# SoC_Control.net
KiCad netlist of a schematic drawn in Altium Designer
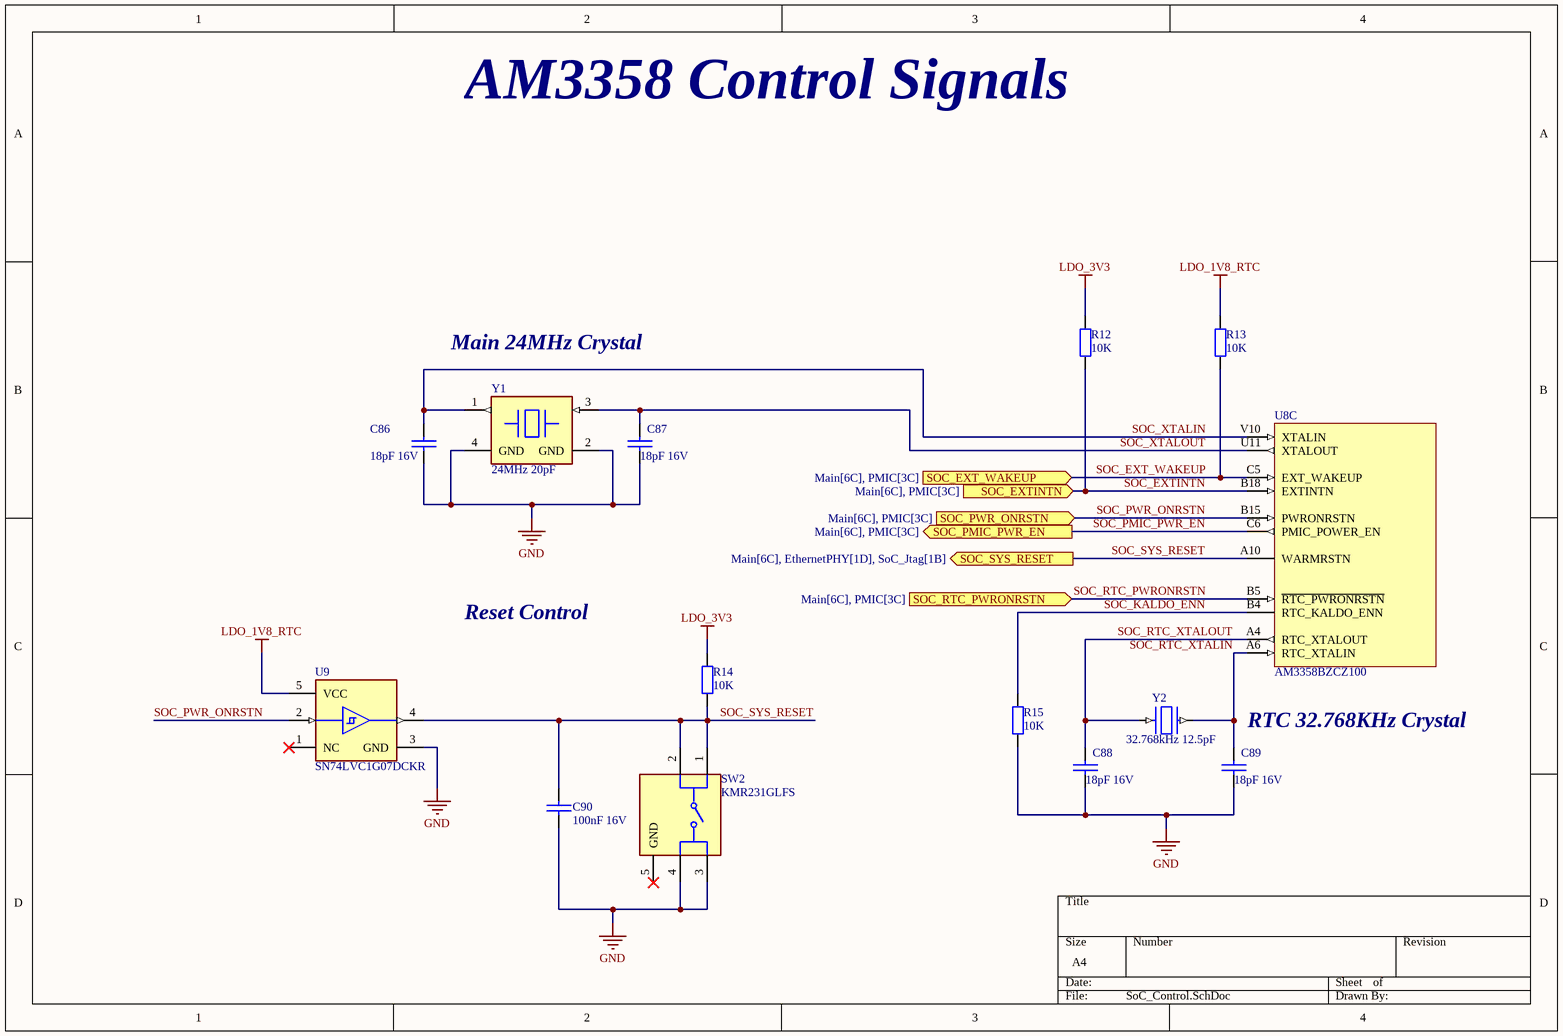
[diagram p0: SoC_Control.SchDoc]

(export (version "E")
  (design (tool "Eeschema 10.0.6"))
  (components
    (comp (ref "C86")
      (value "18pF 16V")
      (footprint "C_0402")
      (description "Capacitor 0402 SMD")
      (libsource (lib "tor1kkLib") (part "C_0402"))
    )
    (comp (ref "C87")
      (value "18pF 16V")
      (footprint "C_0402")
      (description "Capacitor 0402 SMD")
      (libsource (lib "tor1kkLib") (part "C_0402"))
    )
    (comp (ref "C88")
      (value "18pF 16V")
      (footprint "C_0402")
      (description "Capacitor 0402 SMD")
      (libsource (lib "tor1kkLib") (part "C_0402"))
    )
    (comp (ref "C89")
      (value "18pF 16V")
      (footprint "C_0402")
      (description "Capacitor 0402 SMD")
      (libsource (lib "tor1kkLib") (part "C_0402"))
    )
    (comp (ref "C90")
      (value "100nF 16V")
      (footprint "C_0402")
      (description "Capacitor 0402 SMD")
      (libsource (lib "tor1kkLib") (part "C_0402"))
    )
    (comp (ref "R12")
      (value "10K")
      (footprint "R_0402")
      (description "Resistor 0402 SMD")
      (libsource (lib "tor1kkLib") (part "R_0402"))
    )
    (comp (ref "R13")
      (value "10K")
      (footprint "R_0402")
      (description "Resistor 0402 SMD")
      (libsource (lib "tor1kkLib") (part "R_0402"))
    )
    (comp (ref "R14")
      (value "10K")
      (footprint "R_0402")
      (description "Resistor 0402 SMD")
      (libsource (lib "tor1kkLib") (part "R_0402"))
    )
    (comp (ref "R15")
      (value "10K")
      (footprint "R_0402")
      (description "Resistor 0402 SMD")
      (libsource (lib "tor1kkLib") (part "R_0402"))
    )
    (comp (ref "SW2")
      (value "KMR231GLFS")
      (footprint "FP-KMR231GLFS-MFG")
      (description "SWITCH TACTILE SPST-NO 0.05A 32V")
      (libsource (lib "Altium Content Vault") (part "4ba73034ab40b7b0ce053ff7ec1e5b4"))
    )
    (comp (ref "U8")
      (value "AM3358BZCZ100")
      (footprint "BGA324C80P18X18_1500X1500X140")
      (description "ARM-ASeries 1GHz NFBGA-324 Microcontrollers (MCU/MPU/SOC) ROHS")
      (fields (field (name "MANUFACTURER") "Texas Instruments"))
      (libsource (lib "tor1kkLib") (part "AM3358BZCZ100"))
    )
    (comp (ref "U9")
      (value "SN74LVC1G07DCKR")
      (footprint "FP-DCK0005A-IPC_C")
      (description "IC BUFF/DVR NON-INVERT SC70-5")
      (libsource (lib "Altium Content Vault") (part "8ab337023d36144ede9cc3383aed264"))
    )
    (comp (ref "Y1")
      (value "24MHz 20pF")
      (footprint "CRYSTAL_SMD3225-4P")
      (description "24MHz Surface Mount Crystal 20pF ±10ppm ±20ppm SMD3225-4P Crystals ROHS")
      (fields
        (field (name "MANUFACTURER") "YXC Crystal Oscillators")
        (field (name "MANUFACTURER PART NUMBER") "X322524MSB4SI")
      )
      (libsource (lib "tor1kkLib") (part "X322524MSB4SI"))
    )
    (comp (ref "Y2")
      (value "32.768kHz 12.5pF")
      (footprint "CRYSTAL_SMD3215-2P")
      (description "32.768kHz Surface Mount Crystal 12.5pF ±20ppm ±30ppm SMD3215-2P Crystals ROHS")
      (fields
        (field (name "MANUFACTURER") "YXC Crystal Oscillators")
        (field (name "MANUFACTURER PART NUMBER") "XKXGI-SUA-32.768K")
      )
      (libsource (lib "tor1kkLib") (part "XKXGI-SUA-32.768K"))
    )
  )
  (nets
    (net (code "1") (name "/SOC_EXTINTN") (class "Default")
      (node (ref "R12") (pin "1") (pintype "passive"))
      (node (ref "U8") (pin "B18") (pinfunction "EXTINTN_B18") (pintype "input"))
    )
    (net (code "2") (name "/SOC_EXT_WAKEUP") (class "Default")
      (node (ref "R13") (pin "1") (pintype "passive"))
      (node (ref "U8") (pin "C5") (pinfunction "EXT_WAKEUP_C5") (pintype "input"))
    )
    (net (code "3") (name "/SOC_KALDO_ENN") (class "Default")
      (node (ref "R15") (pin "2") (pintype "passive"))
      (node (ref "U8") (pin "B4") (pinfunction "RTC_KALDO_ENN_B4") (pintype "passive"))
    )
    (net (code "4") (name "/SOC_PMIC_PWR_EN") (class "Default")
      (node (ref "U8") (pin "C6") (pinfunction "PMIC_POWER_EN_C6") (pintype "output"))
    )
    (net (code "5") (name "/SOC_PWR_ONRSTN") (class "Default")
      (node (ref "U8") (pin "B15") (pinfunction "PWRONRSTN_B15") (pintype "input"))
      (node (ref "U9") (pin "2") (pinfunction "A_2") (pintype "input"))
    )
    (net (code "6") (name "/SOC_RTC_PWRONRSTN") (class "Default")
      (node (ref "U8") (pin "B5") (pinfunction "~{RTC_PWRONRSTN}_B5") (pintype "input"))
    )
    (net (code "7") (name "/SOC_RTC_XTALIN") (class "Default")
      (node (ref "C89") (pin "2") (pintype "passive"))
      (node (ref "U8") (pin "A6") (pinfunction "RTC_XTALIN_A6") (pintype "input"))
      (node (ref "Y2") (pin "1") (pintype "output"))
    )
    (net (code "8") (name "/SOC_RTC_XTALOUT") (class "Default")
      (node (ref "C88") (pin "2") (pintype "passive"))
      (node (ref "U8") (pin "A4") (pinfunction "RTC_XTALOUT_A4") (pintype "output"))
      (node (ref "Y2") (pin "2") (pintype "input"))
    )
    (net (code "9") (name "/SOC_SYS_RESET") (class "Default")
      (node (ref "C90") (pin "1") (pintype "passive"))
      (node (ref "R14") (pin "1") (pintype "passive"))
      (node (ref "SW2") (pin "1") (pinfunction "1_1") (pintype "passive"))
      (node (ref "SW2") (pin "2") (pinfunction "2_2") (pintype "passive"))
      (node (ref "U8") (pin "A10") (pinfunction "WARMRSTN_A10") (pintype "passive"))
      (node (ref "U9") (pin "4") (pinfunction "Y_4") (pintype "output"))
    )
    (net (code "10") (name "/SOC_XTALIN") (class "Default")
      (node (ref "C86") (pin "2") (pintype "passive"))
      (node (ref "U8") (pin "V10") (pinfunction "XTALIN_V10") (pintype "input"))
      (node (ref "Y1") (pin "1") (pinfunction "CRYSTAL_1_1") (pintype "output"))
    )
    (net (code "11") (name "/SOC_XTALOUT") (class "Default")
      (node (ref "C87") (pin "2") (pintype "passive"))
      (node (ref "U8") (pin "U11") (pinfunction "XTALOUT_U11") (pintype "output"))
      (node (ref "Y1") (pin "3") (pinfunction "CRYSTAL_2_3") (pintype "input"))
    )
    (net (code "12") (name "GND") (class "Default")
      (node (ref "C86") (pin "1") (pintype "passive"))
      (node (ref "C87") (pin "1") (pintype "passive"))
      (node (ref "C88") (pin "1") (pintype "passive"))
      (node (ref "C89") (pin "1") (pintype "passive"))
      (node (ref "C90") (pin "2") (pintype "passive"))
      (node (ref "R15") (pin "1") (pintype "passive"))
      (node (ref "SW2") (pin "3") (pinfunction "3_3") (pintype "passive"))
      (node (ref "SW2") (pin "4") (pinfunction "4_4") (pintype "passive"))
      (node (ref "U9") (pin "3") (pinfunction "GND_3") (pintype "power_in"))
      (node (ref "Y1") (pin "2") (pinfunction "GND_2") (pintype "passive"))
      (node (ref "Y1") (pin "4") (pinfunction "GND_4") (pintype "passive"))
    )
    (net (code "13") (name "LDO_1V8_RTC") (class "Default")
      (node (ref "R13") (pin "2") (pintype "passive"))
      (node (ref "U9") (pin "5") (pinfunction "VCC_5") (pintype "power_in"))
    )
    (net (code "14") (name "LDO_3V3") (class "Default")
      (node (ref "R12") (pin "2") (pintype "passive"))
      (node (ref "R14") (pin "2") (pintype "passive"))
    )
    (net (code "15") (name "unconnected-(SW2-GND-Pad5)") (class "Default")
      (node (ref "SW2") (pin "5") (pinfunction "GND_5") (pintype "power_in+no_connect"))
    )
    (net (code "16") (name "unconnected-(U9-NC-Pad1)") (class "Default")
      (node (ref "U9") (pin "1") (pinfunction "NC_1") (pintype "passive+no_connect"))
    )
  )
)
